# Schematic_v7.net
KiCad netlist of a schematic drawn in EAGLE
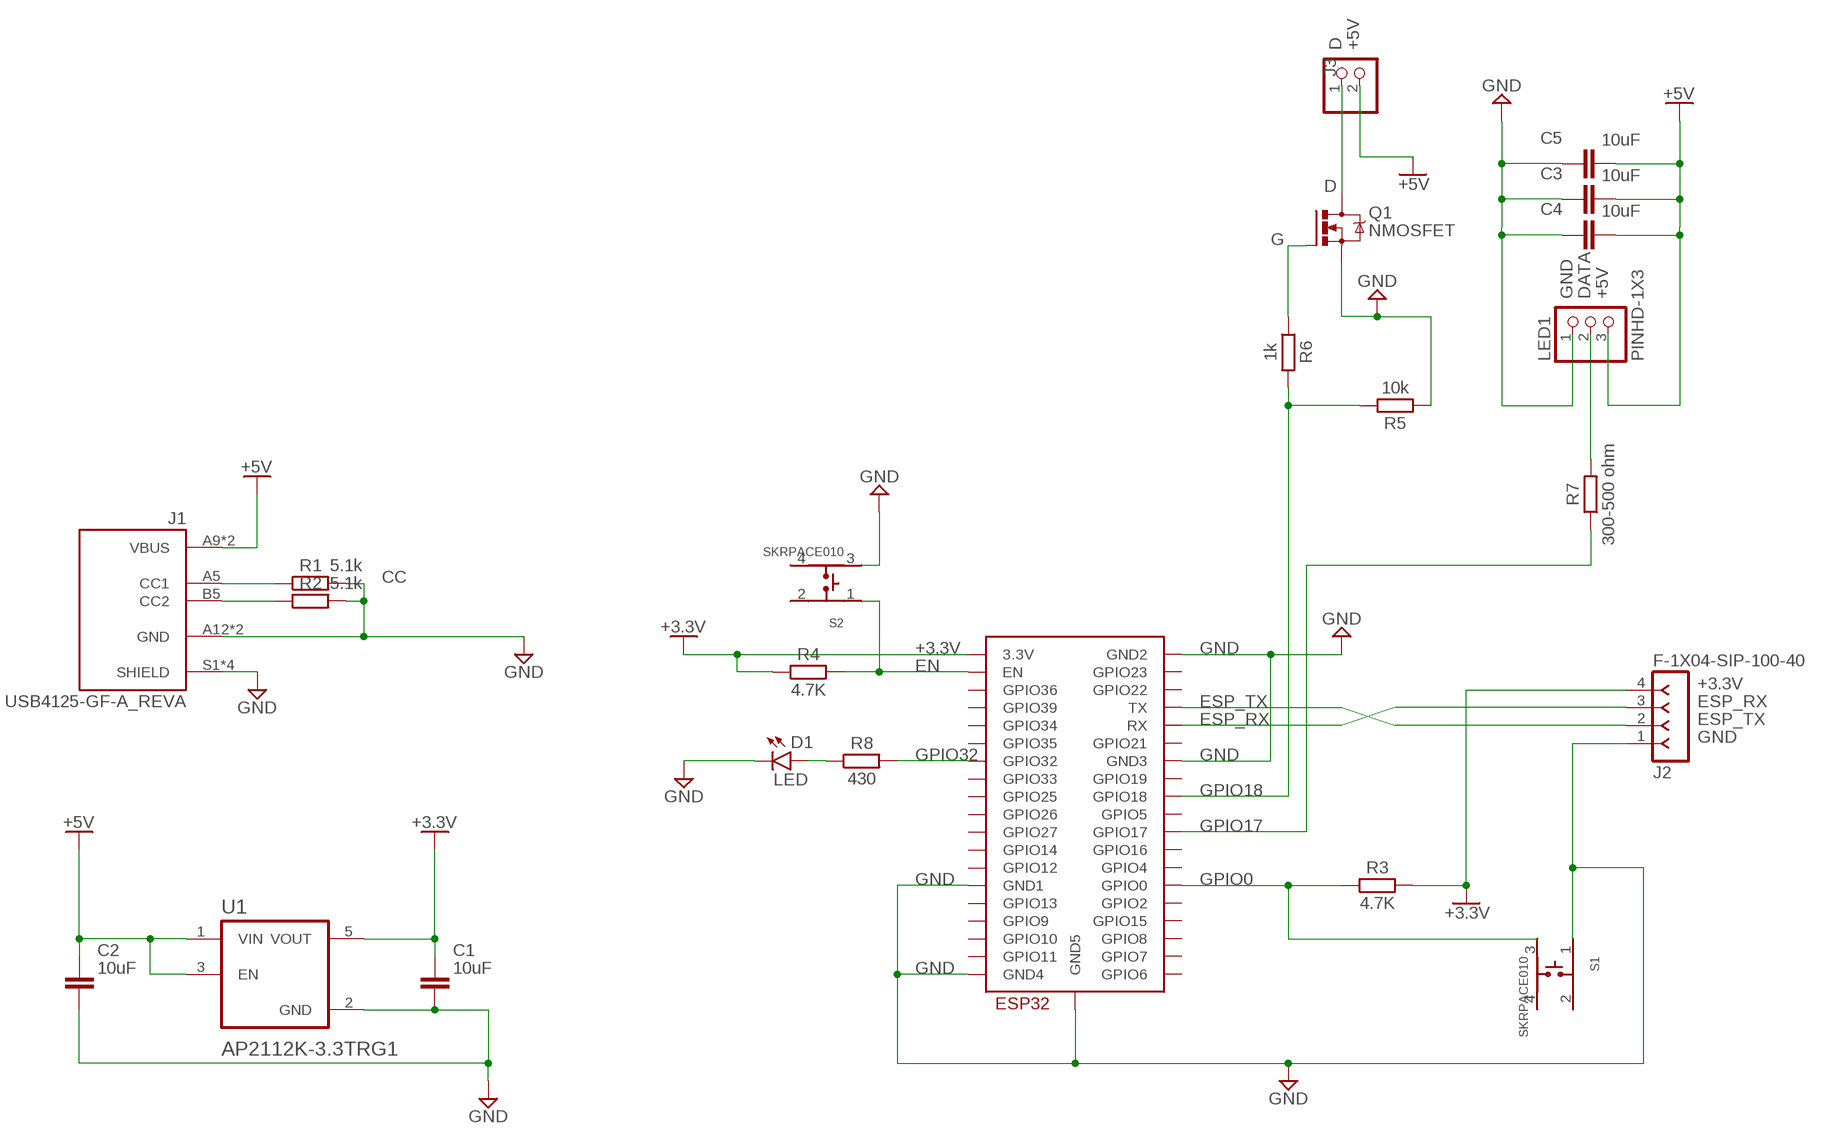
[diagram p0: schematic, sheet 1]

(export (version "E")
  (design (tool "Eeschema 10.0.6"))
  (components
    (comp (ref "C1")
      (value "10uF")
      (footprint "eagle-import:CAPC1608X85")
      (libsource (lib "eagle-import") (part "CCHIP-0603(1608-METRIC)_"))
    )
    (comp (ref "C2")
      (value "10uF")
      (footprint "eagle-import:CAPC1608X85")
      (libsource (lib "eagle-import") (part "CCHIP-0603(1608-METRIC)_"))
    )
    (comp (ref "C3")
      (value "10uF")
      (footprint "eagle-import:CAPC1608X85")
      (libsource (lib "eagle-import") (part "CCHIP-0603(1608-METRIC)_"))
    )
    (comp (ref "C4")
      (value "10uF")
      (footprint "eagle-import:CAPC1608X85")
      (libsource (lib "eagle-import") (part "CCHIP-0603(1608-METRIC)_"))
    )
    (comp (ref "C5")
      (value "10uF")
      (footprint "eagle-import:CAPC1608X85")
      (libsource (lib "eagle-import") (part "CCHIP-0603(1608-METRIC)_"))
    )
    (comp (ref "D1")
      (value "LED")
      (footprint "eagle-import:LEDC1608X80N_FLAT-R")
      (libsource (lib "eagle-import") (part "CHIP-FLAT-R_0603-0.80MM"))
    )
    (comp (ref "J1")
      (value "USB4125-GF-A_REVA")
      (footprint "eagle-import:GCT_USB4125-GF-A_REVA")
      (fields (field (name "MF") "Global Connector Technology") (field (name "MP") "USB4125-GF-A"))
      (libsource (lib "eagle-import") (part "USB4125-GF-A_REVA"))
    )
    (comp (ref "J2")
      (value "F-1X04-SIP-100-40")
      (footprint "eagle-import:SIP-100-04-40")
      (libsource (lib "eagle-import") (part "F-1X04-SIP-100-40"))
    )
    (comp (ref "J3")
      (value "PINHD-1X2")
      (footprint "eagle-import:1X02")
      (libsource (lib "eagle-import") (part "PINHD-1X2"))
    )
    (comp (ref "LED1")
      (value "PINHD-1X3")
      (footprint "eagle-import:1X03")
      (libsource (lib "eagle-import") (part "PINHD-1X3"))
    )
    (comp (ref "Q1")
      (value "NMOSFET")
      (footprint "eagle-import:SOT23")
      (libsource (lib "eagle-import") (part "NMOSFETSOT23_"))
    )
    (comp (ref "R1")
      (value "5.1k")
      (footprint "eagle-import:RESC1608X60")
      (libsource (lib "eagle-import") (part "RCHIP-0603(1608-METRIC)_"))
    )
    (comp (ref "R2")
      (value "5.1k")
      (footprint "eagle-import:RESC1608X60")
      (libsource (lib "eagle-import") (part "RCHIP-0603(1608-METRIC)_"))
    )
    (comp (ref "R3")
      (value "4.7K")
      (footprint "eagle-import:RESC1608X60")
      (libsource (lib "eagle-import") (part "RCHIP-0603(1608-METRIC)_"))
    )
    (comp (ref "R4")
      (value "4.7K")
      (footprint "eagle-import:RESC1608X60")
      (libsource (lib "eagle-import") (part "RCHIP-0603(1608-METRIC)_"))
    )
    (comp (ref "R5")
      (value "10k")
      (footprint "eagle-import:RESC1608X60")
      (libsource (lib "eagle-import") (part "RCHIP-0603(1608-METRIC)_"))
    )
    (comp (ref "R6")
      (value "1k")
      (footprint "eagle-import:RESC1608X60")
      (libsource (lib "eagle-import") (part "RCHIP-0603(1608-METRIC)_"))
    )
    (comp (ref "R7")
      (value "300-500 ohm")
      (footprint "eagle-import:RESC1608X60")
      (libsource (lib "eagle-import") (part "RCHIP-0603(1608-METRIC)_"))
    )
    (comp (ref "R8")
      (value "430")
      (footprint "eagle-import:RESC1608X60")
      (libsource (lib "eagle-import") (part "RCHIP-0603(1608-METRIC)_"))
    )
    (comp (ref "S1")
      (value "SKRPACE010")
      (footprint "eagle-import:SW_SKRPACE010")
      (fields (field (name "MANUFACTURER") "ALPS"))
      (libsource (lib "eagle-import") (part "SKRPACE010"))
    )
    (comp (ref "S2")
      (value "SKRPACE010")
      (footprint "eagle-import:SW_SKRPACE010")
      (fields (field (name "MANUFACTURER") "ALPS"))
      (libsource (lib "eagle-import") (part "SKRPACE010"))
    )
    (comp (ref "U1")
      (value "AP2112K-3.3TRG1")
      (footprint "eagle-import:SOT95P285X140-5N")
      (fields (field (name "MANUFACTURER") "Diodes Inc."))
      (libsource (lib "eagle-import") (part "AP2112K-3.3TRG1"))
    )
    (comp (ref "U2")
      (value "ESP32-WROOM")
      (footprint "eagle-import:ESP32-WROOM")
      (libsource (lib "eagle-import") (part "ESP32-WROOM"))
    )
  )
  (nets
    (net (code "1") (name "+3.3V") (class "Default")
      (node (ref "C1") (pin "1") (pinfunction "1_1") (pintype "passive"))
      (node (ref "J2") (pin "4") (pinfunction "4_4") (pintype "passive"))
      (node (ref "R3") (pin "2") (pinfunction "2_2") (pintype "passive"))
      (node (ref "R4") (pin "1") (pinfunction "1_1") (pintype "passive"))
      (node (ref "U1") (pin "5") (pinfunction "VOUT_5") (pintype "power_in"))
      (node (ref "U2") (pin "3V3") (pinfunction "3.3V_3V3") (pintype "bidirectional"))
    )
    (net (code "2") (name "+5V") (class "Default")
      (node (ref "C2") (pin "1") (pinfunction "1_1") (pintype "passive"))
      (node (ref "C3") (pin "2") (pinfunction "2_2") (pintype "passive"))
      (node (ref "C4") (pin "2") (pinfunction "2_2") (pintype "passive"))
      (node (ref "C5") (pin "2") (pinfunction "2_2") (pintype "passive"))
      (node (ref "J1") (pin "A9") (pinfunction "VBUS_A9") (pintype "power_in"))
      (node (ref "J1") (pin "B9") (pinfunction "VBUS_B9") (pintype "power_in"))
      (node (ref "J3") (pin "2") (pinfunction "2_2") (pintype "passive"))
      (node (ref "LED1") (pin "3") (pinfunction "3_3") (pintype "passive"))
      (node (ref "U1") (pin "1") (pinfunction "VIN_1") (pintype "power_in"))
      (node (ref "U1") (pin "3") (pinfunction "EN_3") (pintype "input"))
    )
    (net (code "3") (name "/CC") (class "Default")
      (node (ref "J1") (pin "A5") (pinfunction "CC1_A5") (pintype "bidirectional"))
      (node (ref "R1") (pin "1") (pinfunction "1_1") (pintype "passive"))
    )
    (net (code "4") (name "/D") (class "Default")
      (node (ref "J3") (pin "1") (pinfunction "1_1") (pintype "passive"))
      (node (ref "Q1") (pin "3") (pinfunction "D_3") (pintype "passive"))
    )
    (net (code "5") (name "/DATA") (class "Default")
      (node (ref "LED1") (pin "2") (pinfunction "2_2") (pintype "passive"))
      (node (ref "R7") (pin "2") (pinfunction "2_2") (pintype "passive"))
    )
    (net (code "6") (name "/EN") (class "Default")
      (node (ref "R4") (pin "2") (pinfunction "2_2") (pintype "passive"))
      (node (ref "S2") (pin "1") (pinfunction "1_1") (pintype "bidirectional"))
      (node (ref "U2") (pin "EN") (pinfunction "EN_EN") (pintype "bidirectional"))
    )
    (net (code "7") (name "/ESP_RX") (class "Default")
      (node (ref "J2") (pin "3") (pinfunction "3_3") (pintype "passive"))
      (node (ref "U2") (pin "RX") (pinfunction "RX_RX") (pintype "bidirectional"))
    )
    (net (code "8") (name "/ESP_TX") (class "Default")
      (node (ref "J2") (pin "2") (pinfunction "2_2") (pintype "passive"))
      (node (ref "U2") (pin "TX") (pinfunction "TX_TX") (pintype "bidirectional"))
    )
    (net (code "9") (name "/G") (class "Default")
      (node (ref "Q1") (pin "1") (pinfunction "G_1") (pintype "passive"))
      (node (ref "R6") (pin "1") (pinfunction "1_1") (pintype "passive"))
    )
    (net (code "10") (name "/GPIO0") (class "Default")
      (node (ref "R3") (pin "1") (pinfunction "1_1") (pintype "passive"))
      (node (ref "S1") (pin "3") (pinfunction "3_3") (pintype "bidirectional"))
      (node (ref "U2") (pin "IO0") (pinfunction "GPIO0_IO0") (pintype "bidirectional"))
    )
    (net (code "11") (name "/GPIO17") (class "Default")
      (node (ref "R7") (pin "1") (pinfunction "1_1") (pintype "passive"))
      (node (ref "U2") (pin "IO17") (pinfunction "GPIO17_IO17") (pintype "bidirectional"))
    )
    (net (code "12") (name "/GPIO18") (class "Default")
      (node (ref "R5") (pin "2") (pinfunction "2_2") (pintype "passive"))
      (node (ref "R6") (pin "2") (pinfunction "2_2") (pintype "passive"))
      (node (ref "U2") (pin "IO18") (pinfunction "GPIO18_IO18") (pintype "bidirectional"))
    )
    (net (code "13") (name "/GPIO32") (class "Default")
      (node (ref "R8") (pin "2") (pinfunction "2_2") (pintype "passive"))
      (node (ref "U2") (pin "IO32") (pinfunction "GPIO32_IO32") (pintype "bidirectional"))
    )
    (net (code "14") (name "GND") (class "Default")
      (node (ref "C1") (pin "2") (pinfunction "2_2") (pintype "passive"))
      (node (ref "C2") (pin "2") (pinfunction "2_2") (pintype "passive"))
      (node (ref "C3") (pin "1") (pinfunction "1_1") (pintype "passive"))
      (node (ref "C4") (pin "1") (pinfunction "1_1") (pintype "passive"))
      (node (ref "C5") (pin "1") (pinfunction "1_1") (pintype "passive"))
      (node (ref "D1") (pin "C") (pinfunction "C_C") (pintype "passive"))
      (node (ref "J1") (pin "A12") (pinfunction "GND_A12") (pintype "power_in"))
      (node (ref "J1") (pin "B12") (pinfunction "GND_B12") (pintype "power_in"))
      (node (ref "J1") (pin "S1") (pinfunction "SHIELD_S1") (pintype "passive"))
      (node (ref "J1") (pin "S2") (pinfunction "SHIELD_S2") (pintype "passive"))
      (node (ref "J1") (pin "S3") (pinfunction "SHIELD_S3") (pintype "passive"))
      (node (ref "J1") (pin "S4") (pinfunction "SHIELD_S4") (pintype "passive"))
      (node (ref "J2") (pin "1") (pinfunction "1_1") (pintype "passive"))
      (node (ref "LED1") (pin "1") (pinfunction "1_1") (pintype "passive"))
      (node (ref "Q1") (pin "2") (pinfunction "S_2") (pintype "passive"))
      (node (ref "R1") (pin "2") (pinfunction "2_2") (pintype "passive"))
      (node (ref "R2") (pin "2") (pinfunction "2_2") (pintype "passive"))
      (node (ref "R5") (pin "1") (pinfunction "1_1") (pintype "passive"))
      (node (ref "S1") (pin "1") (pinfunction "1_1") (pintype "bidirectional"))
      (node (ref "S2") (pin "3") (pinfunction "3_3") (pintype "bidirectional"))
      (node (ref "U1") (pin "2") (pinfunction "GND_2") (pintype "power_in"))
      (node (ref "U2") (pin "GND1") (pinfunction "GND1_GND1") (pintype "bidirectional"))
      (node (ref "U2") (pin "GND2") (pinfunction "GND2_GND2") (pintype "bidirectional"))
      (node (ref "U2") (pin "GND3") (pinfunction "GND3_GND3") (pintype "bidirectional"))
      (node (ref "U2") (pin "GND4") (pinfunction "GND4_GND4") (pintype "bidirectional"))
      (node (ref "U2") (pin "GND5") (pinfunction "GND5_GND5") (pintype "bidirectional"))
    )
    (net (code "15") (name "Net-(D1-PadA)") (class "Default")
      (node (ref "D1") (pin "A") (pinfunction "A_A") (pintype "passive"))
      (node (ref "R8") (pin "1") (pinfunction "1_1") (pintype "passive"))
    )
    (net (code "16") (name "Net-(J1-CC2)") (class "Default")
      (node (ref "J1") (pin "B5") (pinfunction "CC2_B5") (pintype "bidirectional"))
      (node (ref "R2") (pin "1") (pinfunction "1_1") (pintype "passive"))
    )
    (net (code "17") (name "unconnected-(S1-Pad2)") (class "Default")
      (node (ref "S1") (pin "2") (pinfunction "2_2") (pintype "bidirectional"))
    )
    (net (code "18") (name "unconnected-(S1-Pad4)") (class "Default")
      (node (ref "S1") (pin "4") (pinfunction "4_4") (pintype "bidirectional"))
    )
    (net (code "19") (name "unconnected-(S2-Pad2)") (class "Default")
      (node (ref "S2") (pin "2") (pinfunction "2_2") (pintype "bidirectional"))
    )
    (net (code "20") (name "unconnected-(S2-Pad4)") (class "Default")
      (node (ref "S2") (pin "4") (pinfunction "4_4") (pintype "bidirectional"))
    )
    (net (code "21") (name "unconnected-(U2-GPIO2-PadIO2)") (class "Default")
      (node (ref "U2") (pin "IO2") (pinfunction "GPIO2_IO2") (pintype "bidirectional"))
    )
    (net (code "22") (name "unconnected-(U2-GPIO4-PadIO4)") (class "Default")
      (node (ref "U2") (pin "IO4") (pinfunction "GPIO4_IO4") (pintype "bidirectional"))
    )
    (net (code "23") (name "unconnected-(U2-GPIO5-PadIO5)") (class "Default")
      (node (ref "U2") (pin "IO5") (pinfunction "GPIO5_IO5") (pintype "bidirectional"))
    )
    (net (code "24") (name "unconnected-(U2-GPIO6-PadCLK)") (class "Default")
      (node (ref "U2") (pin "CLK") (pinfunction "GPIO6_CLK") (pintype "bidirectional"))
    )
    (net (code "25") (name "unconnected-(U2-GPIO7-PadSD0)") (class "Default")
      (node (ref "U2") (pin "SD0") (pinfunction "GPIO7_SD0") (pintype "bidirectional"))
    )
    (net (code "26") (name "unconnected-(U2-GPIO8-PadSD1)") (class "Default")
      (node (ref "U2") (pin "SD1") (pinfunction "GPIO8_SD1") (pintype "bidirectional"))
    )
    (net (code "27") (name "unconnected-(U2-GPIO9-PadSD2)") (class "Default")
      (node (ref "U2") (pin "SD2") (pinfunction "GPIO9_SD2") (pintype "bidirectional"))
    )
    (net (code "28") (name "unconnected-(U2-GPIO10-PadSD3)") (class "Default")
      (node (ref "U2") (pin "SD3") (pinfunction "GPIO10_SD3") (pintype "bidirectional"))
    )
    (net (code "29") (name "unconnected-(U2-GPIO11-PadCMD)") (class "Default")
      (node (ref "U2") (pin "CMD") (pinfunction "GPIO11_CMD") (pintype "bidirectional"))
    )
    (net (code "30") (name "unconnected-(U2-GPIO12-PadIO12)") (class "Default")
      (node (ref "U2") (pin "IO12") (pinfunction "GPIO12_IO12") (pintype "bidirectional"))
    )
    (net (code "31") (name "unconnected-(U2-GPIO13-PadIO13)") (class "Default")
      (node (ref "U2") (pin "IO13") (pinfunction "GPIO13_IO13") (pintype "bidirectional"))
    )
    (net (code "32") (name "unconnected-(U2-GPIO14-PadIO14)") (class "Default")
      (node (ref "U2") (pin "IO14") (pinfunction "GPIO14_IO14") (pintype "bidirectional"))
    )
    (net (code "33") (name "unconnected-(U2-GPIO15-PadIO15)") (class "Default")
      (node (ref "U2") (pin "IO15") (pinfunction "GPIO15_IO15") (pintype "bidirectional"))
    )
    (net (code "34") (name "unconnected-(U2-GPIO16-PadIO16)") (class "Default")
      (node (ref "U2") (pin "IO16") (pinfunction "GPIO16_IO16") (pintype "bidirectional"))
    )
    (net (code "35") (name "unconnected-(U2-GPIO19-PadIO19)") (class "Default")
      (node (ref "U2") (pin "IO19") (pinfunction "GPIO19_IO19") (pintype "bidirectional"))
    )
    (net (code "36") (name "unconnected-(U2-GPIO21-PadIO21)") (class "Default")
      (node (ref "U2") (pin "IO21") (pinfunction "GPIO21_IO21") (pintype "bidirectional"))
    )
    (net (code "37") (name "unconnected-(U2-GPIO22-PadIO22)") (class "Default")
      (node (ref "U2") (pin "IO22") (pinfunction "GPIO22_IO22") (pintype "bidirectional"))
    )
    (net (code "38") (name "unconnected-(U2-GPIO23-PadIO23)") (class "Default")
      (node (ref "U2") (pin "IO23") (pinfunction "GPIO23_IO23") (pintype "bidirectional"))
    )
    (net (code "39") (name "unconnected-(U2-GPIO25-PadIO25)") (class "Default")
      (node (ref "U2") (pin "IO25") (pinfunction "GPIO25_IO25") (pintype "bidirectional"))
    )
    (net (code "40") (name "unconnected-(U2-GPIO26-PadIO26)") (class "Default")
      (node (ref "U2") (pin "IO26") (pinfunction "GPIO26_IO26") (pintype "bidirectional"))
    )
    (net (code "41") (name "unconnected-(U2-GPIO27-PadIO27)") (class "Default")
      (node (ref "U2") (pin "IO27") (pinfunction "GPIO27_IO27") (pintype "bidirectional"))
    )
    (net (code "42") (name "unconnected-(U2-GPIO33-PadIO33)") (class "Default")
      (node (ref "U2") (pin "IO33") (pinfunction "GPIO33_IO33") (pintype "bidirectional"))
    )
    (net (code "43") (name "unconnected-(U2-GPIO34-PadIO34)") (class "Default")
      (node (ref "U2") (pin "IO34") (pinfunction "GPIO34_IO34") (pintype "bidirectional"))
    )
    (net (code "44") (name "unconnected-(U2-GPIO35-PadIO35)") (class "Default")
      (node (ref "U2") (pin "IO35") (pinfunction "GPIO35_IO35") (pintype "bidirectional"))
    )
    (net (code "45") (name "unconnected-(U2-GPIO36-PadSENSOR_VP)") (class "Default")
      (node (ref "U2") (pin "SENSOR_VP") (pinfunction "GPIO36_SENSOR_VP") (pintype "bidirectional"))
    )
    (net (code "46") (name "unconnected-(U2-GPIO39-PadSENSOR_VN)") (class "Default")
      (node (ref "U2") (pin "SENSOR_VN") (pinfunction "GPIO39_SENSOR_VN") (pintype "bidirectional"))
    )
  )
)
